# isolationScaleSMD.net
KiCad netlist of a schematic drawn in Altium Designer
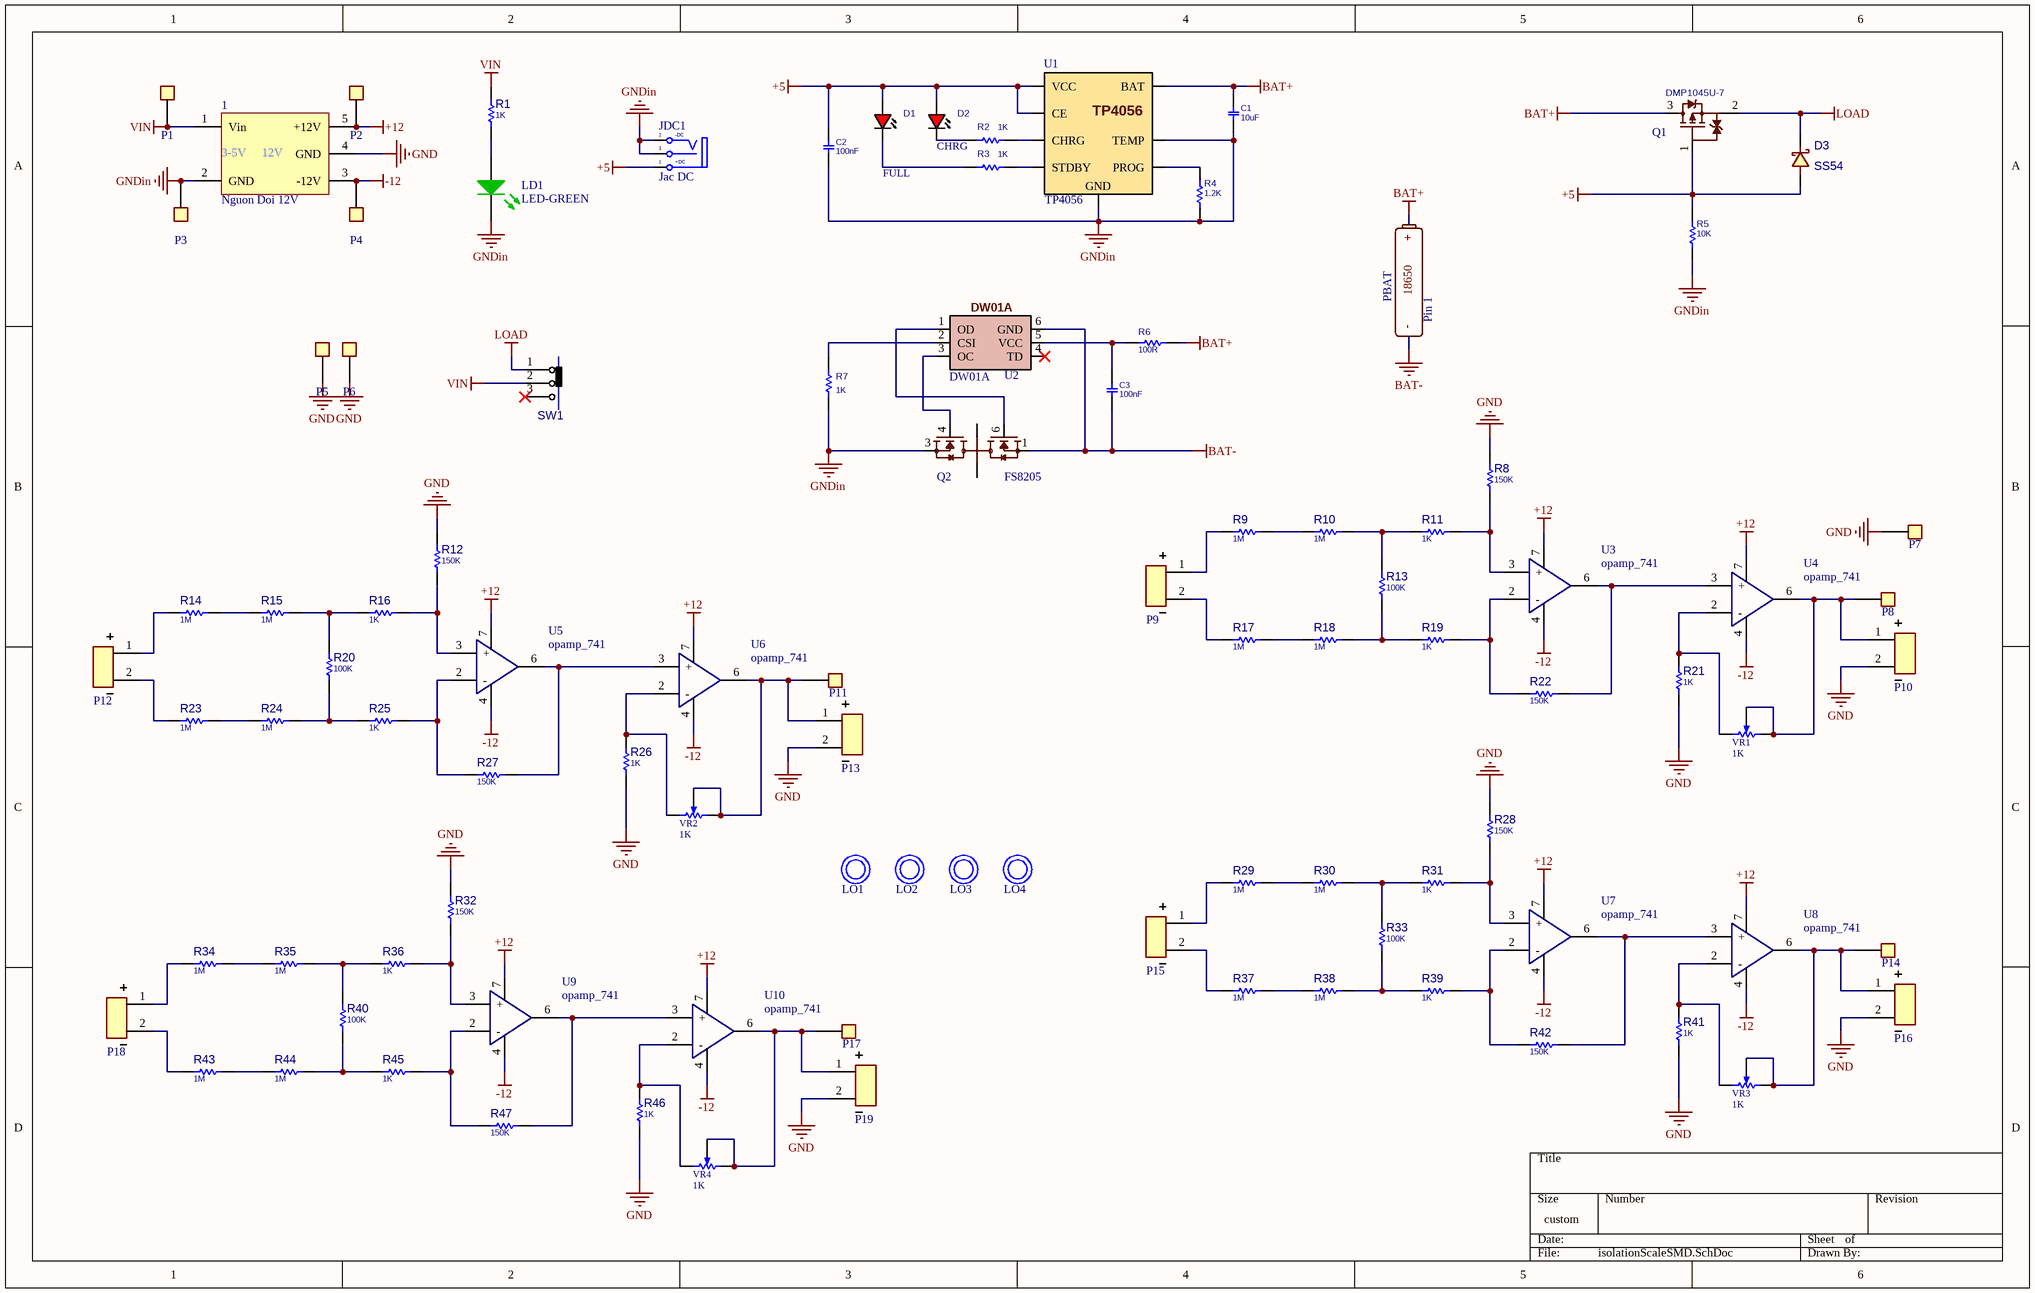
[diagram p0: isolationScaleSMD.SchDoc]

(export (version "E")
  (design (tool "Eeschema 10.0.6"))
  (components
    (comp (ref "1")
      (value "Nguon Doi 12V")
      (footprint "isolationScaleSMD_V4 - Copy:5V_+-12V")
      (description "Nguon Doi +-12V")
      (libsource (lib "IoT") (part "Nguon Doi +-12V"))
    )
    (comp (ref "C1")
      (value "10uF")
      (footprint "cap_0805")
      (description "CAP SMD")
      (fields (field (name "MANF_P#") "MANF_PART#"))
      (libsource (lib "IoT") (part "CAP SMD"))
    )
    (comp (ref "C2")
      (value "100nF")
      (footprint "cap_0805")
      (description "CAP SMD")
      (fields (field (name "MANF_P#") "MANF_PART#"))
      (libsource (lib "IoT") (part "CAP SMD"))
    )
    (comp (ref "C3")
      (value "100nF")
      (footprint "cap_0805")
      (description "CAP SMD")
      (fields (field (name "MANF_P#") "MANF_PART#"))
      (libsource (lib "IoT") (part "CAP SMD"))
    )
    (comp (ref "D1")
      (value "FULL")
      (footprint "LED0805RED")
      (description "LED, SMD, 0805, RED")
      (fields (field (name "MANF") "MANF") (field (name "MANF_P#") "MANF_PART#"))
      (libsource (lib "IoT") (part "LED_SMD_0805_RED"))
    )
    (comp (ref "D2")
      (value "CHRG")
      (footprint "LED0805RED")
      (description "LED, SMD, 0805, RED")
      (fields (field (name "MANF") "MANF") (field (name "MANF_P#") "MANF_PART#"))
      (libsource (lib "IoT") (part "LED_SMD_0805_RED"))
    )
    (comp (ref "D3")
      (value "SS54")
      (footprint "D_SMA")
      (description "DIODE, SCHOTTKY, 40V, 3A")
      (fields (field (name "MANF") "Diodes") (field (name "MANF_P#") "1N5822"))
      (libsource (lib "IoT") (part "DIODE_THD_SCHOTTKY_1N5822"))
    )
    (comp (ref "JDC1")
      (value "Jac DC")
      (footprint "DC-IN")
      (description "Jac DC input")
      (libsource (lib "IoT") (part "DCIN"))
    )
    (comp (ref "LD1")
      (value "LED-GREEN")
      (footprint "isolationScaleSMD_V4 - Copy:LED RED 0805")
      (description "LED GREEN CLEAR 0603 SMD")
      (libsource (lib "isolationScaleSMD") (part "LED_LTST-C191KGKT_1"))
    )
    (comp (ref "LO1") (value "LO KHOAN") (footprint "SCMH_M3P5FT") (libsource (lib "IoT") (part "LO KHOAN")))
    (comp (ref "LO2") (value "LO KHOAN") (footprint "SCMH_M3P5FT") (libsource (lib "IoT") (part "LO KHOAN")))
    (comp (ref "LO3") (value "LO KHOAN") (footprint "SCMH_M3P5FT") (libsource (lib "IoT") (part "LO KHOAN")))
    (comp (ref "LO4") (value "LO KHOAN") (footprint "SCMH_M3P5FT") (libsource (lib "IoT") (part "LO KHOAN")))
    (comp (ref "P1")
      (value "test PCB")
      (footprint "tp_red_1p")
      (description "testpin")
      (libsource (lib "") (part "test PCB_1"))
    )
    (comp (ref "P2")
      (value "test PCB")
      (footprint "tp_red_1p")
      (description "testpin")
      (libsource (lib "") (part "test PCB_1"))
    )
    (comp (ref "P3")
      (value "test PCB")
      (footprint "Tp_black_1p")
      (description "testpin")
      (libsource (lib "isolationScaleSMD") (part "test PCB"))
    )
    (comp (ref "P4")
      (value "test PCB")
      (footprint "tp_red_1p")
      (description "testpin")
      (libsource (lib "isolationScaleSMD") (part "test PCB"))
    )
    (comp (ref "P5")
      (value "test PCB")
      (footprint "Tp_black_1p")
      (description "testpin")
      (libsource (lib "") (part "test PCB_1"))
    )
    (comp (ref "P6")
      (value "test PCB")
      (footprint "Tp_black_1p")
      (description "testpin")
      (libsource (lib "") (part "test PCB_1"))
    )
    (comp (ref "P7")
      (value "test PCB")
      (footprint "Tp_black_1p")
      (description "testpin")
      (libsource (lib "IoT") (part "test PCB"))
    )
    (comp (ref "P8")
      (value "test PCB")
      (footprint "tp_red_1p")
      (description "testpin")
      (libsource (lib "IoT") (part "test PCB"))
    )
    (comp (ref "P9") (value "BNC_2p") (footprint "BNC_2p") (libsource (lib "") (part "BNC_2p_1")))
    (comp (ref "P10") (value "BNC_2p") (footprint "BNC_2p") (libsource (lib "IoT") (part "BNC_2p")))
    (comp (ref "P11")
      (value "test PCB")
      (footprint "tp_red_1p")
      (description "testpin")
      (libsource (lib "IoT") (part "test PCB"))
    )
    (comp (ref "P12") (value "BNC_2p") (footprint "BNC_2p") (libsource (lib "") (part "BNC_2p_1")))
    (comp (ref "P13") (value "BNC_2p") (footprint "BNC_2p") (libsource (lib "IoT") (part "BNC_2p")))
    (comp (ref "P14")
      (value "test PCB")
      (footprint "tp_red_1p")
      (description "testpin")
      (libsource (lib "IoT") (part "test PCB"))
    )
    (comp (ref "P15") (value "BNC_2p") (footprint "BNC_2p") (libsource (lib "") (part "BNC_2p_1")))
    (comp (ref "P16") (value "BNC_2p") (footprint "BNC_2p") (libsource (lib "IoT") (part "BNC_2p")))
    (comp (ref "P17")
      (value "test PCB")
      (footprint "tp_red_1p")
      (description "testpin")
      (libsource (lib "IoT") (part "test PCB"))
    )
    (comp (ref "P18") (value "BNC_2p") (footprint "BNC_2p") (libsource (lib "") (part "BNC_2p_1")))
    (comp (ref "P19") (value "BNC_2p") (footprint "BNC_2p") (libsource (lib "IoT") (part "BNC_2p")))
    (comp (ref "Pin 1")
      (value "PBAT")
      (footprint "Pin 18650 1 cell")
      (description "Pin 18650")
      (libsource (lib "IoT") (part "Pin 18650"))
    )
    (comp (ref "Q1")
      (value "DMP1045U-7")
      (footprint "SOT91P240X110-3N")
      (description "MOSFET DMP1045U-7 P Channel")
      (fields (field (name "MANF_P#") "IRF5305"))
      (libsource (lib "IoT") (part "MOSFET DMP1045U-7"))
    )
    (comp (ref "Q2")
      (value "FS8205")
      (footprint "SOT23-6")
      (description "Dual N-Channel Enhancement Mode Power MOSFET")
      (fields (field (name "MF") "Fortune Semiconductor"))
      (libsource (lib "IoT") (part "FS8205"))
    )
    (comp (ref "R1")
      (value "1K")
      (footprint "R0805")
      (description "RESISTOR, SMD, SENS, 0.01Ohm, 0.5W")
      (fields (field (name "MANF_P#") "WSLP0805R0100FEA") (field (name "MANF") "VISHAY"))
      (libsource (lib "isolationScaleSMD") (part "RES_SMD_0805"))
    )
    (comp (ref "R2")
      (value "1K")
      (footprint "R0805")
      (description "RES SMD")
      (fields (field (name "MANF_P#") "WSLP0805R0100FEA") (field (name "MANF") "VISHAY"))
      (libsource (lib "IoT") (part "RES SMD"))
    )
    (comp (ref "R3")
      (value "1K")
      (footprint "R0805")
      (description "RES SMD")
      (fields (field (name "MANF_P#") "WSLP0805R0100FEA") (field (name "MANF") "VISHAY"))
      (libsource (lib "IoT") (part "RES SMD"))
    )
    (comp (ref "R4")
      (value "1.2K")
      (footprint "R0805")
      (description "RES SMD")
      (fields (field (name "MANF_P#") "WSLP0805R0100FEA") (field (name "MANF") "VISHAY"))
      (libsource (lib "IoT") (part "RES SMD"))
    )
    (comp (ref "R5")
      (value "10K")
      (footprint "R0805")
      (description "RES SMD")
      (fields (field (name "MANF_P#") "WSLP0805R0100FEA") (field (name "MANF") "VISHAY"))
      (libsource (lib "IoT") (part "RES SMD"))
    )
    (comp (ref "R6")
      (value "100R")
      (footprint "R0805")
      (description "RES SMD")
      (fields (field (name "MANF_P#") "WSLP0805R0100FEA") (field (name "MANF") "VISHAY"))
      (libsource (lib "IoT") (part "RES SMD"))
    )
    (comp (ref "R7")
      (value "1K")
      (footprint "R0805")
      (description "RES SMD")
      (fields (field (name "MANF_P#") "WSLP0805R0100FEA") (field (name "MANF") "VISHAY"))
      (libsource (lib "IoT") (part "RES SMD"))
    )
    (comp (ref "R8")
      (value "150K")
      (footprint "R0805")
      (description "RESISTOR, SMD, SENS, 0.01Ohm, 0.5W")
      (fields (field (name "MANF_P#") "WSLP0805R0100FEA") (field (name "MANF") "VISHAY"))
      (libsource (lib "IoT") (part "RES_SMD_0805"))
    )
    (comp (ref "R9")
      (value "1M")
      (footprint "R0805")
      (description "RESISTOR, SMD, SENS, 0.01Ohm, 0.5W")
      (fields (field (name "MANF_P#") "WSLP0805R0100FEA") (field (name "MANF") "VISHAY"))
      (libsource (lib "IoT") (part "RES_SMD_0805"))
    )
    (comp (ref "R10")
      (value "1M")
      (footprint "R0805")
      (description "RESISTOR, SMD, SENS, 0.01Ohm, 0.5W")
      (fields (field (name "MANF_P#") "WSLP0805R0100FEA") (field (name "MANF") "VISHAY"))
      (libsource (lib "IoT") (part "RES_SMD_0805"))
    )
    (comp (ref "R11")
      (value "1K")
      (footprint "R0805")
      (description "RESISTOR, SMD, SENS, 0.01Ohm, 0.5W")
      (fields (field (name "MANF_P#") "WSLP0805R0100FEA") (field (name "MANF") "VISHAY"))
      (libsource (lib "IoT") (part "RES_SMD_0805"))
    )
    (comp (ref "R12")
      (value "150K")
      (footprint "R0805")
      (description "RESISTOR, SMD, SENS, 0.01Ohm, 0.5W")
      (fields (field (name "MANF_P#") "WSLP0805R0100FEA") (field (name "MANF") "VISHAY"))
      (libsource (lib "IoT") (part "RES_SMD_0805"))
    )
    (comp (ref "R13")
      (value "100K")
      (footprint "R0805")
      (description "RESISTOR, SMD, SENS, 0.01Ohm, 0.5W")
      (fields (field (name "MANF_P#") "WSLP0805R0100FEA") (field (name "MANF") "VISHAY"))
      (libsource (lib "IoT") (part "RES_SMD_0805"))
    )
    (comp (ref "R14")
      (value "1M")
      (footprint "R0805")
      (description "RESISTOR, SMD, SENS, 0.01Ohm, 0.5W")
      (fields (field (name "MANF_P#") "WSLP0805R0100FEA") (field (name "MANF") "VISHAY"))
      (libsource (lib "IoT") (part "RES_SMD_0805"))
    )
    (comp (ref "R15")
      (value "1M")
      (footprint "R0805")
      (description "RESISTOR, SMD, SENS, 0.01Ohm, 0.5W")
      (fields (field (name "MANF_P#") "WSLP0805R0100FEA") (field (name "MANF") "VISHAY"))
      (libsource (lib "IoT") (part "RES_SMD_0805"))
    )
    (comp (ref "R16")
      (value "1K")
      (footprint "R0805")
      (description "RESISTOR, SMD, SENS, 0.01Ohm, 0.5W")
      (fields (field (name "MANF_P#") "WSLP0805R0100FEA") (field (name "MANF") "VISHAY"))
      (libsource (lib "IoT") (part "RES_SMD_0805"))
    )
    (comp (ref "R17")
      (value "1M")
      (footprint "R0805")
      (description "RESISTOR, SMD, SENS, 0.01Ohm, 0.5W")
      (fields (field (name "MANF_P#") "WSLP0805R0100FEA") (field (name "MANF") "VISHAY"))
      (libsource (lib "IoT") (part "RES_SMD_0805"))
    )
    (comp (ref "R18")
      (value "1M")
      (footprint "R0805")
      (description "RESISTOR, SMD, SENS, 0.01Ohm, 0.5W")
      (fields (field (name "MANF_P#") "WSLP0805R0100FEA") (field (name "MANF") "VISHAY"))
      (libsource (lib "IoT") (part "RES_SMD_0805"))
    )
    (comp (ref "R19")
      (value "1K")
      (footprint "R0805")
      (description "RESISTOR, SMD, SENS, 0.01Ohm, 0.5W")
      (fields (field (name "MANF_P#") "WSLP0805R0100FEA") (field (name "MANF") "VISHAY"))
      (libsource (lib "IoT") (part "RES_SMD_0805"))
    )
    (comp (ref "R20")
      (value "100K")
      (footprint "R0805")
      (description "RESISTOR, SMD, SENS, 0.01Ohm, 0.5W")
      (fields (field (name "MANF_P#") "WSLP0805R0100FEA") (field (name "MANF") "VISHAY"))
      (libsource (lib "IoT") (part "RES_SMD_0805"))
    )
    (comp (ref "R21")
      (value "1K")
      (footprint "R0805")
      (description "RESISTOR, SMD, SENS, 0.01Ohm, 0.5W")
      (fields (field (name "MANF_P#") "WSLP0805R0100FEA") (field (name "MANF") "VISHAY"))
      (libsource (lib "IoT") (part "RES_SMD_0805"))
    )
    (comp (ref "R22")
      (value "150K")
      (footprint "R0805")
      (description "RESISTOR, SMD, SENS, 0.01Ohm, 0.5W")
      (fields (field (name "MANF_P#") "WSLP0805R0100FEA") (field (name "MANF") "VISHAY"))
      (libsource (lib "IoT") (part "RES_SMD_0805"))
    )
    (comp (ref "R23")
      (value "1M")
      (footprint "R0805")
      (description "RESISTOR, SMD, SENS, 0.01Ohm, 0.5W")
      (fields (field (name "MANF_P#") "WSLP0805R0100FEA") (field (name "MANF") "VISHAY"))
      (libsource (lib "IoT") (part "RES_SMD_0805"))
    )
    (comp (ref "R24")
      (value "1M")
      (footprint "R0805")
      (description "RESISTOR, SMD, SENS, 0.01Ohm, 0.5W")
      (fields (field (name "MANF_P#") "WSLP0805R0100FEA") (field (name "MANF") "VISHAY"))
      (libsource (lib "IoT") (part "RES_SMD_0805"))
    )
    (comp (ref "R25")
      (value "1K")
      (footprint "R0805")
      (description "RESISTOR, SMD, SENS, 0.01Ohm, 0.5W")
      (fields (field (name "MANF_P#") "WSLP0805R0100FEA") (field (name "MANF") "VISHAY"))
      (libsource (lib "IoT") (part "RES_SMD_0805"))
    )
    (comp (ref "R26")
      (value "1K")
      (footprint "R0805")
      (description "RESISTOR, SMD, SENS, 0.01Ohm, 0.5W")
      (fields (field (name "MANF_P#") "WSLP0805R0100FEA") (field (name "MANF") "VISHAY"))
      (libsource (lib "IoT") (part "RES_SMD_0805"))
    )
    (comp (ref "R27")
      (value "150K")
      (footprint "R0805")
      (description "RESISTOR, SMD, SENS, 0.01Ohm, 0.5W")
      (fields (field (name "MANF_P#") "WSLP0805R0100FEA") (field (name "MANF") "VISHAY"))
      (libsource (lib "IoT") (part "RES_SMD_0805"))
    )
    (comp (ref "R28")
      (value "150K")
      (footprint "R0805")
      (description "RESISTOR, SMD, SENS, 0.01Ohm, 0.5W")
      (fields (field (name "MANF_P#") "WSLP0805R0100FEA") (field (name "MANF") "VISHAY"))
      (libsource (lib "IoT") (part "RES_SMD_0805"))
    )
    (comp (ref "R29")
      (value "1M")
      (footprint "R0805")
      (description "RESISTOR, SMD, SENS, 0.01Ohm, 0.5W")
      (fields (field (name "MANF_P#") "WSLP0805R0100FEA") (field (name "MANF") "VISHAY"))
      (libsource (lib "IoT") (part "RES_SMD_0805"))
    )
    (comp (ref "R30")
      (value "1M")
      (footprint "R0805")
      (description "RESISTOR, SMD, SENS, 0.01Ohm, 0.5W")
      (fields (field (name "MANF_P#") "WSLP0805R0100FEA") (field (name "MANF") "VISHAY"))
      (libsource (lib "IoT") (part "RES_SMD_0805"))
    )
    (comp (ref "R31")
      (value "1K")
      (footprint "R0805")
      (description "RESISTOR, SMD, SENS, 0.01Ohm, 0.5W")
      (fields (field (name "MANF_P#") "WSLP0805R0100FEA") (field (name "MANF") "VISHAY"))
      (libsource (lib "IoT") (part "RES_SMD_0805"))
    )
    (comp (ref "R32")
      (value "150K")
      (footprint "R0805")
      (description "RESISTOR, SMD, SENS, 0.01Ohm, 0.5W")
      (fields (field (name "MANF_P#") "WSLP0805R0100FEA") (field (name "MANF") "VISHAY"))
      (libsource (lib "IoT") (part "RES_SMD_0805"))
    )
    (comp (ref "R33")
      (value "100K")
      (footprint "R0805")
      (description "RESISTOR, SMD, SENS, 0.01Ohm, 0.5W")
      (fields (field (name "MANF_P#") "WSLP0805R0100FEA") (field (name "MANF") "VISHAY"))
      (libsource (lib "IoT") (part "RES_SMD_0805"))
    )
    (comp (ref "R34")
      (value "1M")
      (footprint "R0805")
      (description "RESISTOR, SMD, SENS, 0.01Ohm, 0.5W")
      (fields (field (name "MANF_P#") "WSLP0805R0100FEA") (field (name "MANF") "VISHAY"))
      (libsource (lib "IoT") (part "RES_SMD_0805"))
    )
    (comp (ref "R35")
      (value "1M")
      (footprint "R0805")
      (description "RESISTOR, SMD, SENS, 0.01Ohm, 0.5W")
      (fields (field (name "MANF_P#") "WSLP0805R0100FEA") (field (name "MANF") "VISHAY"))
      (libsource (lib "IoT") (part "RES_SMD_0805"))
    )
    (comp (ref "R36")
      (value "1K")
      (footprint "R0805")
      (description "RESISTOR, SMD, SENS, 0.01Ohm, 0.5W")
      (fields (field (name "MANF_P#") "WSLP0805R0100FEA") (field (name "MANF") "VISHAY"))
      (libsource (lib "IoT") (part "RES_SMD_0805"))
    )
    (comp (ref "R37")
      (value "1M")
      (footprint "R0805")
      (description "RESISTOR, SMD, SENS, 0.01Ohm, 0.5W")
      (fields (field (name "MANF_P#") "WSLP0805R0100FEA") (field (name "MANF") "VISHAY"))
      (libsource (lib "IoT") (part "RES_SMD_0805"))
    )
    (comp (ref "R38")
      (value "1M")
      (footprint "R0805")
      (description "RESISTOR, SMD, SENS, 0.01Ohm, 0.5W")
      (fields (field (name "MANF_P#") "WSLP0805R0100FEA") (field (name "MANF") "VISHAY"))
      (libsource (lib "IoT") (part "RES_SMD_0805"))
    )
    (comp (ref "R39")
      (value "1K")
      (footprint "R0805")
      (description "RESISTOR, SMD, SENS, 0.01Ohm, 0.5W")
      (fields (field (name "MANF_P#") "WSLP0805R0100FEA") (field (name "MANF") "VISHAY"))
      (libsource (lib "IoT") (part "RES_SMD_0805"))
    )
    (comp (ref "R40")
      (value "100K")
      (footprint "R0805")
      (description "RESISTOR, SMD, SENS, 0.01Ohm, 0.5W")
      (fields (field (name "MANF_P#") "WSLP0805R0100FEA") (field (name "MANF") "VISHAY"))
      (libsource (lib "IoT") (part "RES_SMD_0805"))
    )
    (comp (ref "R41")
      (value "1K")
      (footprint "R0805")
      (description "RESISTOR, SMD, SENS, 0.01Ohm, 0.5W")
      (fields (field (name "MANF_P#") "WSLP0805R0100FEA") (field (name "MANF") "VISHAY"))
      (libsource (lib "IoT") (part "RES_SMD_0805"))
    )
    (comp (ref "R42")
      (value "150K")
      (footprint "R0805")
      (description "RESISTOR, SMD, SENS, 0.01Ohm, 0.5W")
      (fields (field (name "MANF_P#") "WSLP0805R0100FEA") (field (name "MANF") "VISHAY"))
      (libsource (lib "IoT") (part "RES_SMD_0805"))
    )
    (comp (ref "R43")
      (value "1M")
      (footprint "R0805")
      (description "RESISTOR, SMD, SENS, 0.01Ohm, 0.5W")
      (fields (field (name "MANF_P#") "WSLP0805R0100FEA") (field (name "MANF") "VISHAY"))
      (libsource (lib "IoT") (part "RES_SMD_0805"))
    )
    (comp (ref "R44")
      (value "1M")
      (footprint "R0805")
      (description "RESISTOR, SMD, SENS, 0.01Ohm, 0.5W")
      (fields (field (name "MANF_P#") "WSLP0805R0100FEA") (field (name "MANF") "VISHAY"))
      (libsource (lib "IoT") (part "RES_SMD_0805"))
    )
    (comp (ref "R45")
      (value "1K")
      (footprint "R0805")
      (description "RESISTOR, SMD, SENS, 0.01Ohm, 0.5W")
      (fields (field (name "MANF_P#") "WSLP0805R0100FEA") (field (name "MANF") "VISHAY"))
      (libsource (lib "IoT") (part "RES_SMD_0805"))
    )
    (comp (ref "R46")
      (value "1K")
      (footprint "R0805")
      (description "RESISTOR, SMD, SENS, 0.01Ohm, 0.5W")
      (fields (field (name "MANF_P#") "WSLP0805R0100FEA") (field (name "MANF") "VISHAY"))
      (libsource (lib "IoT") (part "RES_SMD_0805"))
    )
    (comp (ref "R47")
      (value "150K")
      (footprint "R0805")
      (description "RESISTOR, SMD, SENS, 0.01Ohm, 0.5W")
      (fields (field (name "MANF_P#") "WSLP0805R0100FEA") (field (name "MANF") "VISHAY"))
      (libsource (lib "IoT") (part "RES_SMD_0805"))
    )
    (comp (ref "SW1")
      (value "SlideSwitch")
      (footprint "SWSLIDT_SPDT_S_8X4")
      (description "SWITCH, SLIDE, SPDT, 8.6X4.3mm, THD")
      (fields (field (name "MANF") "C&K") (field (name "MANF_PART#") "OS102011MS2QN1"))
      (libsource (lib "IoT") (part "SWSLIDT_SPDT_S_8X4"))
    )
    (comp (ref "U1")
      (value "TP4056")
      (footprint "isolationScaleSMD_V4 - Copy1:SOP-8127P600X175-9N")
      (libsource (lib "IoT") (part "TP4056"))
    )
    (comp (ref "U2") (value "DW01A") (footprint "SOT23-6") (libsource (lib "IoT") (part "DW01A")))
    (comp (ref "U3")
      (value "opamp_741")
      (footprint "DIP-8_2.54_8_t/h")
      (libsource (lib "IoT") (part "opamp LM741"))
    )
    (comp (ref "U4")
      (value "opamp_741")
      (footprint "DIP-8_2.54_8_t/h")
      (libsource (lib "IoT") (part "opamp LM741"))
    )
    (comp (ref "U5")
      (value "opamp_741")
      (footprint "DIP-8_2.54_8_t/h")
      (libsource (lib "IoT") (part "opamp LM741"))
    )
    (comp (ref "U6")
      (value "opamp_741")
      (footprint "DIP-8_2.54_8_t/h")
      (libsource (lib "IoT") (part "opamp LM741"))
    )
    (comp (ref "U7")
      (value "opamp_741")
      (footprint "DIP-8_2.54_8_t/h")
      (libsource (lib "IoT") (part "opamp LM741"))
    )
    (comp (ref "U8")
      (value "opamp_741")
      (footprint "DIP-8_2.54_8_t/h")
      (libsource (lib "IoT") (part "opamp LM741"))
    )
    (comp (ref "U9")
      (value "opamp_741")
      (footprint "DIP-8_2.54_8_t/h")
      (libsource (lib "IoT") (part "opamp LM741"))
    )
    (comp (ref "U10")
      (value "opamp_741")
      (footprint "DIP-8_2.54_8_t/h")
      (libsource (lib "IoT") (part "opamp LM741"))
    )
    (comp (ref "VR1")
      (value "1K")
      (footprint "VARIABLE RESISTOR_3362P")
      (description "Square Trimming Potentiometer")
      (libsource (lib "IoT") (part "Variable Resistor"))
    )
    (comp (ref "VR2")
      (value "1K")
      (footprint "VARIABLE RESISTOR_3362P")
      (description "Square Trimming Potentiometer")
      (libsource (lib "IoT") (part "Variable Resistor"))
    )
    (comp (ref "VR3")
      (value "1K")
      (footprint "VARIABLE RESISTOR_3362P")
      (description "Square Trimming Potentiometer")
      (libsource (lib "IoT") (part "Variable Resistor"))
    )
    (comp (ref "VR4")
      (value "1K")
      (footprint "VARIABLE RESISTOR_3362P")
      (description "Square Trimming Potentiometer")
      (libsource (lib "IoT") (part "Variable Resistor"))
    )
  )
  (nets
    (net (code "1") (name "+5") (class "Default")
      (node (ref "C2") (pin "2") (pinfunction "2_2") (pintype "passive"))
      (node (ref "D1") (pin "1") (pinfunction "ANODE_1") (pintype "passive"))
      (node (ref "D2") (pin "1") (pinfunction "ANODE_1") (pintype "passive"))
      (node (ref "D3") (pin "1") (pinfunction "A_1") (pintype "passive"))
      (node (ref "JDC1") (pin "1") (pinfunction "T_1") (pintype "passive"))
      (node (ref "Q1") (pin "1") (pinfunction "G_1") (pintype "passive"))
      (node (ref "R5") (pin "2") (pinfunction "2_2") (pintype "passive"))
      (node (ref "U1") (pin "4") (pinfunction "VCC_4") (pintype "passive"))
      (node (ref "U1") (pin "8") (pinfunction "CE_8") (pintype "passive"))
    )
    (net (code "2") (name "+12") (class "Default")
      (node (ref "1") (pin "5") (pinfunction "+12V_5") (pintype "passive"))
      (node (ref "P2") (pin "1") (pinfunction "1_1") (pintype "power_in"))
      (node (ref "U10") (pin "7") (pinfunction "VCC_7") (pintype "passive"))
      (node (ref "U3") (pin "7") (pinfunction "VCC_7") (pintype "passive"))
      (node (ref "U4") (pin "7") (pinfunction "VCC_7") (pintype "passive"))
      (node (ref "U5") (pin "7") (pinfunction "VCC_7") (pintype "passive"))
      (node (ref "U6") (pin "7") (pinfunction "VCC_7") (pintype "passive"))
      (node (ref "U7") (pin "7") (pinfunction "VCC_7") (pintype "passive"))
      (node (ref "U8") (pin "7") (pinfunction "VCC_7") (pintype "passive"))
      (node (ref "U9") (pin "7") (pinfunction "VCC_7") (pintype "passive"))
    )
    (net (code "3") (name "-12") (class "Default")
      (node (ref "1") (pin "3") (pinfunction "-12V_3") (pintype "passive"))
      (node (ref "P4") (pin "1") (pinfunction "1_1") (pintype "power_in"))
      (node (ref "U10") (pin "4") (pinfunction "GND_4") (pintype "passive"))
      (node (ref "U3") (pin "4") (pinfunction "GND_4") (pintype "passive"))
      (node (ref "U4") (pin "4") (pinfunction "GND_4") (pintype "passive"))
      (node (ref "U5") (pin "4") (pinfunction "GND_4") (pintype "passive"))
      (node (ref "U6") (pin "4") (pinfunction "GND_4") (pintype "passive"))
      (node (ref "U7") (pin "4") (pinfunction "GND_4") (pintype "passive"))
      (node (ref "U8") (pin "4") (pinfunction "GND_4") (pintype "passive"))
      (node (ref "U9") (pin "4") (pinfunction "GND_4") (pintype "passive"))
    )
    (net (code "4") (name "BAT+") (class "Default")
      (node (ref "C1") (pin "2") (pinfunction "2_2") (pintype "passive"))
      (node (ref "Pin 1") (pin "1") (pinfunction "Bat+_1") (pintype "passive"))
      (node (ref "Q1") (pin "3") (pinfunction "D_3") (pintype "passive"))
      (node (ref "R6") (pin "1") (pinfunction "1_1") (pintype "passive"))
      (node (ref "U1") (pin "5") (pinfunction "BAT_5") (pintype "passive"))
    )
    (net (code "5") (name "BAT-") (class "Default")
      (node (ref "C3") (pin "1") (pinfunction "1_1") (pintype "passive"))
      (node (ref "Pin 1") (pin "2") (pinfunction "Bat-_2") (pintype "passive"))
      (node (ref "Q2") (pin "1") (pinfunction "S1_1") (pintype "passive"))
      (node (ref "U2") (pin "6") (pinfunction "GND_6") (pintype "passive"))
    )
    (net (code "6") (name "GND") (class "Default")
      (node (ref "1") (pin "4") (pinfunction "GND_4") (pintype "passive"))
      (node (ref "P10") (pin "2") (pinfunction "2_2") (pintype "power_in"))
      (node (ref "P13") (pin "2") (pinfunction "2_2") (pintype "power_in"))
      (node (ref "P16") (pin "2") (pinfunction "2_2") (pintype "power_in"))
      (node (ref "P19") (pin "2") (pinfunction "2_2") (pintype "power_in"))
      (node (ref "P5") (pin "1") (pinfunction "1_1") (pintype "power_in"))
      (node (ref "P6") (pin "1") (pinfunction "1_1") (pintype "power_in"))
      (node (ref "P7") (pin "1") (pinfunction "1_1") (pintype "power_in"))
      (node (ref "R12") (pin "2") (pinfunction "2_2") (pintype "passive"))
      (node (ref "R21") (pin "1") (pinfunction "1_1") (pintype "passive"))
      (node (ref "R26") (pin "1") (pinfunction "1_1") (pintype "passive"))
      (node (ref "R28") (pin "2") (pinfunction "2_2") (pintype "passive"))
      (node (ref "R32") (pin "2") (pinfunction "2_2") (pintype "passive"))
      (node (ref "R41") (pin "1") (pinfunction "1_1") (pintype "passive"))
      (node (ref "R46") (pin "1") (pinfunction "1_1") (pintype "passive"))
      (node (ref "R8") (pin "2") (pinfunction "2_2") (pintype "passive"))
    )
    (net (code "7") (name "GNDin") (class "Default")
      (node (ref "1") (pin "2") (pinfunction "GND_2") (pintype "passive"))
      (node (ref "C1") (pin "1") (pinfunction "1_1") (pintype "passive"))
      (node (ref "C2") (pin "1") (pinfunction "1_1") (pintype "passive"))
      (node (ref "JDC1") (pin "2") (pinfunction "TN_2") (pintype "passive"))
      (node (ref "JDC1") (pin "3") (pinfunction "S_3") (pintype "power_in"))
      (node (ref "LD1") (pin "2") (pinfunction "K_2") (pintype "passive"))
      (node (ref "P3") (pin "1") (pinfunction "1_1") (pintype "power_in"))
      (node (ref "Q2") (pin "3") (pinfunction "S2_3") (pintype "passive"))
      (node (ref "R4") (pin "1") (pinfunction "1_1") (pintype "passive"))
      (node (ref "R5") (pin "1") (pinfunction "1_1") (pintype "passive"))
      (node (ref "R7") (pin "1") (pinfunction "1_1") (pintype "passive"))
      (node (ref "U1") (pin "1") (pinfunction "TEMP_1") (pintype "passive"))
      (node (ref "U1") (pin "3") (pinfunction "FEEDBACK_3") (pintype "passive"))
    )
    (net (code "8") (name "LOAD") (class "Default")
      (node (ref "D3") (pin "2") (pinfunction "K_2") (pintype "passive"))
      (node (ref "Q1") (pin "2") (pinfunction "S_2") (pintype "passive"))
      (node (ref "SW1") (pin "1") (pinfunction "P1_1") (pintype "passive"))
    )
    (net (code "9") (name "Net-(D1-CATHODE)") (class "Default")
      (node (ref "D1") (pin "2") (pinfunction "CATHODE_2") (pintype "passive"))
      (node (ref "R3") (pin "1") (pinfunction "1_1") (pintype "passive"))
    )
    (net (code "10") (name "Net-(D2-CATHODE)") (class "Default")
      (node (ref "D2") (pin "2") (pinfunction "CATHODE_2") (pintype "passive"))
      (node (ref "R2") (pin "1") (pinfunction "1_1") (pintype "passive"))
    )
    (net (code "11") (name "Net-(LD1-A)") (class "Default")
      (node (ref "LD1") (pin "1") (pinfunction "A_1") (pintype "passive"))
      (node (ref "R1") (pin "1") (pinfunction "1_1") (pintype "passive"))
    )
    (net (code "12") (name "Net-(P9-Pad1)") (class "Default")
      (node (ref "P9") (pin "1") (pinfunction "1_1") (pintype "power_in"))
      (node (ref "R9") (pin "1") (pinfunction "1_1") (pintype "passive"))
    )
    (net (code "13") (name "Net-(P9-Pad2)") (class "Default")
      (node (ref "P9") (pin "2") (pinfunction "2_2") (pintype "power_in"))
      (node (ref "R17") (pin "1") (pinfunction "1_1") (pintype "passive"))
    )
    (net (code "14") (name "Net-(P12-Pad1)") (class "Default")
      (node (ref "P12") (pin "1") (pinfunction "1_1") (pintype "power_in"))
      (node (ref "R14") (pin "1") (pinfunction "1_1") (pintype "passive"))
    )
    (net (code "15") (name "Net-(P12-Pad2)") (class "Default")
      (node (ref "P12") (pin "2") (pinfunction "2_2") (pintype "power_in"))
      (node (ref "R23") (pin "1") (pinfunction "1_1") (pintype "passive"))
    )
    (net (code "16") (name "Net-(P15-Pad1)") (class "Default")
      (node (ref "P15") (pin "1") (pinfunction "1_1") (pintype "power_in"))
      (node (ref "R29") (pin "1") (pinfunction "1_1") (pintype "passive"))
    )
    (net (code "17") (name "Net-(P15-Pad2)") (class "Default")
      (node (ref "P15") (pin "2") (pinfunction "2_2") (pintype "power_in"))
      (node (ref "R37") (pin "1") (pinfunction "1_1") (pintype "passive"))
    )
    (net (code "18") (name "Net-(P18-Pad1)") (class "Default")
      (node (ref "P18") (pin "1") (pinfunction "1_1") (pintype "power_in"))
      (node (ref "R34") (pin "1") (pinfunction "1_1") (pintype "passive"))
    )
    (net (code "19") (name "Net-(P18-Pad2)") (class "Default")
      (node (ref "P18") (pin "2") (pinfunction "2_2") (pintype "power_in"))
      (node (ref "R43") (pin "1") (pinfunction "1_1") (pintype "passive"))
    )
    (net (code "20") (name "Net-(Q2-D12-Pad2)_1") (class "Default")
      (node (ref "Q2") (pin "2") (pinfunction "D12_2") (pintype "passive"))
      (node (ref "Q2") (pin "5") (pinfunction "D12_5") (pintype "passive"))
    )
    (net (code "21") (name "Net-(Q2-G1)") (class "Default")
      (node (ref "Q2") (pin "6") (pinfunction "G1_6") (pintype "passive"))
      (node (ref "U2") (pin "1") (pinfunction "OD_1") (pintype "passive"))
    )
    (net (code "22") (name "Net-(Q2-G2)") (class "Default")
      (node (ref "Q2") (pin "4") (pinfunction "G2_4") (pintype "passive"))
      (node (ref "U2") (pin "3") (pinfunction "OC_3") (pintype "passive"))
    )
    (net (code "23") (name "Net-(R10-Pad1)") (class "Default")
      (node (ref "R10") (pin "1") (pinfunction "1_1") (pintype "passive"))
      (node (ref "R9") (pin "2") (pinfunction "2_2") (pintype "passive"))
    )
    (net (code "24") (name "Net-(R10-Pad2)") (class "Default")
      (node (ref "R10") (pin "2") (pinfunction "2_2") (pintype "passive"))
      (node (ref "R11") (pin "1") (pinfunction "1_1") (pintype "passive"))
      (node (ref "R13") (pin "2") (pinfunction "2_2") (pintype "passive"))
    )
    (net (code "25") (name "Net-(R13-Pad1)") (class "Default")
      (node (ref "R13") (pin "1") (pinfunction "1_1") (pintype "passive"))
      (node (ref "R18") (pin "2") (pinfunction "2_2") (pintype "passive"))
      (node (ref "R19") (pin "1") (pinfunction "1_1") (pintype "passive"))
    )
    (net (code "26") (name "Net-(R14-Pad2)") (class "Default")
      (node (ref "R14") (pin "2") (pinfunction "2_2") (pintype "passive"))
      (node (ref "R15") (pin "1") (pinfunction "1_1") (pintype "passive"))
    )
    (net (code "27") (name "Net-(R15-Pad2)") (class "Default")
      (node (ref "R15") (pin "2") (pinfunction "2_2") (pintype "passive"))
      (node (ref "R16") (pin "1") (pinfunction "1_1") (pintype "passive"))
      (node (ref "R20") (pin "2") (pinfunction "2_2") (pintype "passive"))
    )
    (net (code "28") (name "Net-(R17-Pad2)") (class "Default")
      (node (ref "R17") (pin "2") (pinfunction "2_2") (pintype "passive"))
      (node (ref "R18") (pin "1") (pinfunction "1_1") (pintype "passive"))
    )
    (net (code "29") (name "Net-(R20-Pad1)") (class "Default")
      (node (ref "R20") (pin "1") (pinfunction "1_1") (pintype "passive"))
      (node (ref "R24") (pin "2") (pinfunction "2_2") (pintype "passive"))
      (node (ref "R25") (pin "1") (pinfunction "1_1") (pintype "passive"))
    )
    (net (code "30") (name "Net-(R23-Pad2)") (class "Default")
      (node (ref "R23") (pin "2") (pinfunction "2_2") (pintype "passive"))
      (node (ref "R24") (pin "1") (pinfunction "1_1") (pintype "passive"))
    )
    (net (code "31") (name "Net-(R29-Pad2)") (class "Default")
      (node (ref "R29") (pin "2") (pinfunction "2_2") (pintype "passive"))
      (node (ref "R30") (pin "1") (pinfunction "1_1") (pintype "passive"))
    )
    (net (code "32") (name "Net-(R30-Pad2)") (class "Default")
      (node (ref "R30") (pin "2") (pinfunction "2_2") (pintype "passive"))
      (node (ref "R31") (pin "1") (pinfunction "1_1") (pintype "passive"))
      (node (ref "R33") (pin "2") (pinfunction "2_2") (pintype "passive"))
    )
    (net (code "33") (name "Net-(R33-Pad1)") (class "Default")
      (node (ref "R33") (pin "1") (pinfunction "1_1") (pintype "passive"))
      (node (ref "R38") (pin "2") (pinfunction "2_2") (pintype "passive"))
      (node (ref "R39") (pin "1") (pinfunction "1_1") (pintype "passive"))
    )
    (net (code "34") (name "Net-(R34-Pad2)") (class "Default")
      (node (ref "R34") (pin "2") (pinfunction "2_2") (pintype "passive"))
      (node (ref "R35") (pin "1") (pinfunction "1_1") (pintype "passive"))
    )
    (net (code "35") (name "Net-(R35-Pad2)") (class "Default")
      (node (ref "R35") (pin "2") (pinfunction "2_2") (pintype "passive"))
      (node (ref "R36") (pin "1") (pinfunction "1_1") (pintype "passive"))
      (node (ref "R40") (pin "2") (pinfunction "2_2") (pintype "passive"))
    )
    (net (code "36") (name "Net-(R37-Pad2)") (class "Default")
      (node (ref "R37") (pin "2") (pinfunction "2_2") (pintype "passive"))
      (node (ref "R38") (pin "1") (pinfunction "1_1") (pintype "passive"))
    )
    (net (code "37") (name "Net-(R40-Pad1)") (class "Default")
      (node (ref "R40") (pin "1") (pinfunction "1_1") (pintype "passive"))
      (node (ref "R44") (pin "2") (pinfunction "2_2") (pintype "passive"))
      (node (ref "R45") (pin "1") (pinfunction "1_1") (pintype "passive"))
    )
    (net (code "38") (name "Net-(R43-Pad2)") (class "Default")
      (node (ref "R43") (pin "2") (pinfunction "2_2") (pintype "passive"))
      (node (ref "R44") (pin "1") (pinfunction "1_1") (pintype "passive"))
    )
    (net (code "39") (name "Net-(U1-CHRG)") (class "Default")
      (node (ref "R2") (pin "2") (pinfunction "2_2") (pintype "passive"))
      (node (ref "U1") (pin "7") (pinfunction "CHRG_7") (pintype "passive"))
    )
    (net (code "40") (name "Net-(U1-PROG)") (class "Default")
      (node (ref "R4") (pin "2") (pinfunction "2_2") (pintype "passive"))
      (node (ref "U1") (pin "2") (pinfunction "PROG_2") (pintype "passive"))
    )
    (net (code "41") (name "Net-(U1-STDBY)") (class "Default")
      (node (ref "R3") (pin "2") (pinfunction "2_2") (pintype "passive"))
      (node (ref "U1") (pin "6") (pinfunction "STDBY_6") (pintype "passive"))
    )
    (net (code "42") (name "Net-(U2-CSI)") (class "Default")
      (node (ref "R7") (pin "2") (pinfunction "2_2") (pintype "passive"))
      (node (ref "U2") (pin "2") (pinfunction "CSI_2") (pintype "passive"))
    )
    (net (code "43") (name "Net-(U2-VCC)") (class "Default")
      (node (ref "C3") (pin "2") (pinfunction "2_2") (pintype "passive"))
      (node (ref "R6") (pin "2") (pinfunction "2_2") (pintype "passive"))
      (node (ref "U2") (pin "5") (pinfunction "VCC_5") (pintype "passive"))
    )
    (net (code "44") (name "Net-(U3-+)") (class "Default")
      (node (ref "R11") (pin "2") (pinfunction "2_2") (pintype "passive"))
      (node (ref "R8") (pin "1") (pinfunction "1_1") (pintype "passive"))
      (node (ref "U3") (pin "3") (pinfunction "+_3") (pintype "passive"))
    )
    (net (code "45") (name "Net-(U3--)") (class "Default")
      (node (ref "R19") (pin "2") (pinfunction "2_2") (pintype "passive"))
      (node (ref "R22") (pin "2") (pinfunction "2_2") (pintype "passive"))
      (node (ref "U3") (pin "2") (pinfunction "-_2") (pintype "passive"))
    )
    (net (code "46") (name "Net-(U3-OUT)") (class "Default")
      (node (ref "R22") (pin "1") (pinfunction "1_1") (pintype "passive"))
      (node (ref "U3") (pin "6") (pinfunction "OUT_6") (pintype "passive"))
      (node (ref "U4") (pin "3") (pinfunction "+_3") (pintype "passive"))
    )
    (net (code "47") (name "Net-(U4--)") (class "Default")
      (node (ref "R21") (pin "2") (pinfunction "2_2") (pintype "passive"))
      (node (ref "U4") (pin "2") (pinfunction "-_2") (pintype "passive"))
      (node (ref "VR1") (pin "1") (pinfunction "1_1") (pintype "passive"))
    )
    (net (code "48") (name "Net-(U4-OUT)") (class "Default")
      (node (ref "P10") (pin "1") (pinfunction "1_1") (pintype "power_in"))
      (node (ref "P8") (pin "1") (pinfunction "1_1") (pintype "power_in"))
      (node (ref "U4") (pin "6") (pinfunction "OUT_6") (pintype "passive"))
      (node (ref "VR1") (pin "2") (pinfunction "2_2") (pintype "passive"))
      (node (ref "VR1") (pin "3") (pinfunction "3_3") (pintype "passive"))
    )
    (net (code "49") (name "Net-(U5-+)") (class "Default")
      (node (ref "R12") (pin "1") (pinfunction "1_1") (pintype "passive"))
      (node (ref "R16") (pin "2") (pinfunction "2_2") (pintype "passive"))
      (node (ref "U5") (pin "3") (pinfunction "+_3") (pintype "passive"))
    )
    (net (code "50") (name "Net-(U5--)") (class "Default")
      (node (ref "R25") (pin "2") (pinfunction "2_2") (pintype "passive"))
      (node (ref "R27") (pin "2") (pinfunction "2_2") (pintype "passive"))
      (node (ref "U5") (pin "2") (pinfunction "-_2") (pintype "passive"))
    )
    (net (code "51") (name "Net-(U5-OUT)") (class "Default")
      (node (ref "R27") (pin "1") (pinfunction "1_1") (pintype "passive"))
      (node (ref "U5") (pin "6") (pinfunction "OUT_6") (pintype "passive"))
      (node (ref "U6") (pin "3") (pinfunction "+_3") (pintype "passive"))
    )
    (net (code "52") (name "Net-(U6--)") (class "Default")
      (node (ref "R26") (pin "2") (pinfunction "2_2") (pintype "passive"))
      (node (ref "U6") (pin "2") (pinfunction "-_2") (pintype "passive"))
      (node (ref "VR2") (pin "1") (pinfunction "1_1") (pintype "passive"))
    )
    (net (code "53") (name "Net-(U6-OUT)") (class "Default")
      (node (ref "P11") (pin "1") (pinfunction "1_1") (pintype "power_in"))
      (node (ref "P13") (pin "1") (pinfunction "1_1") (pintype "power_in"))
      (node (ref "U6") (pin "6") (pinfunction "OUT_6") (pintype "passive"))
      (node (ref "VR2") (pin "2") (pinfunction "2_2") (pintype "passive"))
      (node (ref "VR2") (pin "3") (pinfunction "3_3") (pintype "passive"))
    )
    (net (code "54") (name "Net-(U7-+)") (class "Default")
      (node (ref "R28") (pin "1") (pinfunction "1_1") (pintype "passive"))
      (node (ref "R31") (pin "2") (pinfunction "2_2") (pintype "passive"))
      (node (ref "U7") (pin "3") (pinfunction "+_3") (pintype "passive"))
    )
    (net (code "55") (name "Net-(U7--)") (class "Default")
      (node (ref "R39") (pin "2") (pinfunction "2_2") (pintype "passive"))
      (node (ref "R42") (pin "2") (pinfunction "2_2") (pintype "passive"))
      (node (ref "U7") (pin "2") (pinfunction "-_2") (pintype "passive"))
    )
    (net (code "56") (name "Net-(U7-OUT)") (class "Default")
      (node (ref "R42") (pin "1") (pinfunction "1_1") (pintype "passive"))
      (node (ref "U7") (pin "6") (pinfunction "OUT_6") (pintype "passive"))
      (node (ref "U8") (pin "3") (pinfunction "+_3") (pintype "passive"))
    )
    (net (code "57") (name "Net-(U8--)") (class "Default")
      (node (ref "R41") (pin "2") (pinfunction "2_2") (pintype "passive"))
      (node (ref "U8") (pin "2") (pinfunction "-_2") (pintype "passive"))
      (node (ref "VR3") (pin "1") (pinfunction "1_1") (pintype "passive"))
    )
    (net (code "58") (name "Net-(U8-OUT)") (class "Default")
      (node (ref "P14") (pin "1") (pinfunction "1_1") (pintype "power_in"))
      (node (ref "P16") (pin "1") (pinfunction "1_1") (pintype "power_in"))
      (node (ref "U8") (pin "6") (pinfunction "OUT_6") (pintype "passive"))
      (node (ref "VR3") (pin "2") (pinfunction "2_2") (pintype "passive"))
      (node (ref "VR3") (pin "3") (pinfunction "3_3") (pintype "passive"))
    )
    (net (code "59") (name "Net-(U9-+)") (class "Default")
      (node (ref "R32") (pin "1") (pinfunction "1_1") (pintype "passive"))
      (node (ref "R36") (pin "2") (pinfunction "2_2") (pintype "passive"))
      (node (ref "U9") (pin "3") (pinfunction "+_3") (pintype "passive"))
    )
    (net (code "60") (name "Net-(U9--)") (class "Default")
      (node (ref "R45") (pin "2") (pinfunction "2_2") (pintype "passive"))
      (node (ref "R47") (pin "2") (pinfunction "2_2") (pintype "passive"))
      (node (ref "U9") (pin "2") (pinfunction "-_2") (pintype "passive"))
    )
    (net (code "61") (name "Net-(U10-+)") (class "Default")
      (node (ref "R47") (pin "1") (pinfunction "1_1") (pintype "passive"))
      (node (ref "U10") (pin "3") (pinfunction "+_3") (pintype "passive"))
      (node (ref "U9") (pin "6") (pinfunction "OUT_6") (pintype "passive"))
    )
    (net (code "62") (name "Net-(U10--)") (class "Default")
      (node (ref "R46") (pin "2") (pinfunction "2_2") (pintype "passive"))
      (node (ref "U10") (pin "2") (pinfunction "-_2") (pintype "passive"))
      (node (ref "VR4") (pin "1") (pinfunction "1_1") (pintype "passive"))
    )
    (net (code "63") (name "Net-(U10-OUT)") (class "Default")
      (node (ref "P17") (pin "1") (pinfunction "1_1") (pintype "power_in"))
      (node (ref "P19") (pin "1") (pinfunction "1_1") (pintype "power_in"))
      (node (ref "U10") (pin "6") (pinfunction "OUT_6") (pintype "passive"))
      (node (ref "VR4") (pin "2") (pinfunction "2_2") (pintype "passive"))
      (node (ref "VR4") (pin "3") (pinfunction "3_3") (pintype "passive"))
    )
    (net (code "64") (name "VIN") (class "Default")
      (node (ref "1") (pin "1") (pinfunction "Vin_1") (pintype "passive"))
      (node (ref "P1") (pin "1") (pinfunction "1_1") (pintype "power_in"))
      (node (ref "R1") (pin "2") (pinfunction "2_2") (pintype "passive"))
      (node (ref "SW1") (pin "2") (pinfunction "P3_2") (pintype "passive"))
    )
    (net (code "65") (name "unconnected-(Q2-D12-Pad2)") (class "Default")
      (node (ref "Q2") (pin "2") (pinfunction "D12_2") (pintype "passive"))
    )
    (net (code "66") (name "unconnected-(SW1-P4-Pad3)") (class "Default")
      (node (ref "SW1") (pin "3") (pinfunction "P4_3") (pintype "passive+no_connect"))
    )
    (net (code "67") (name "unconnected-(U2-TD-Pad4)") (class "Default")
      (node (ref "U2") (pin "4") (pinfunction "TD_4") (pintype "passive+no_connect"))
    )
  )
)
